# 15_FE_PORT_1-8.net
KiCad netlist of a schematic drawn in Altium Designer
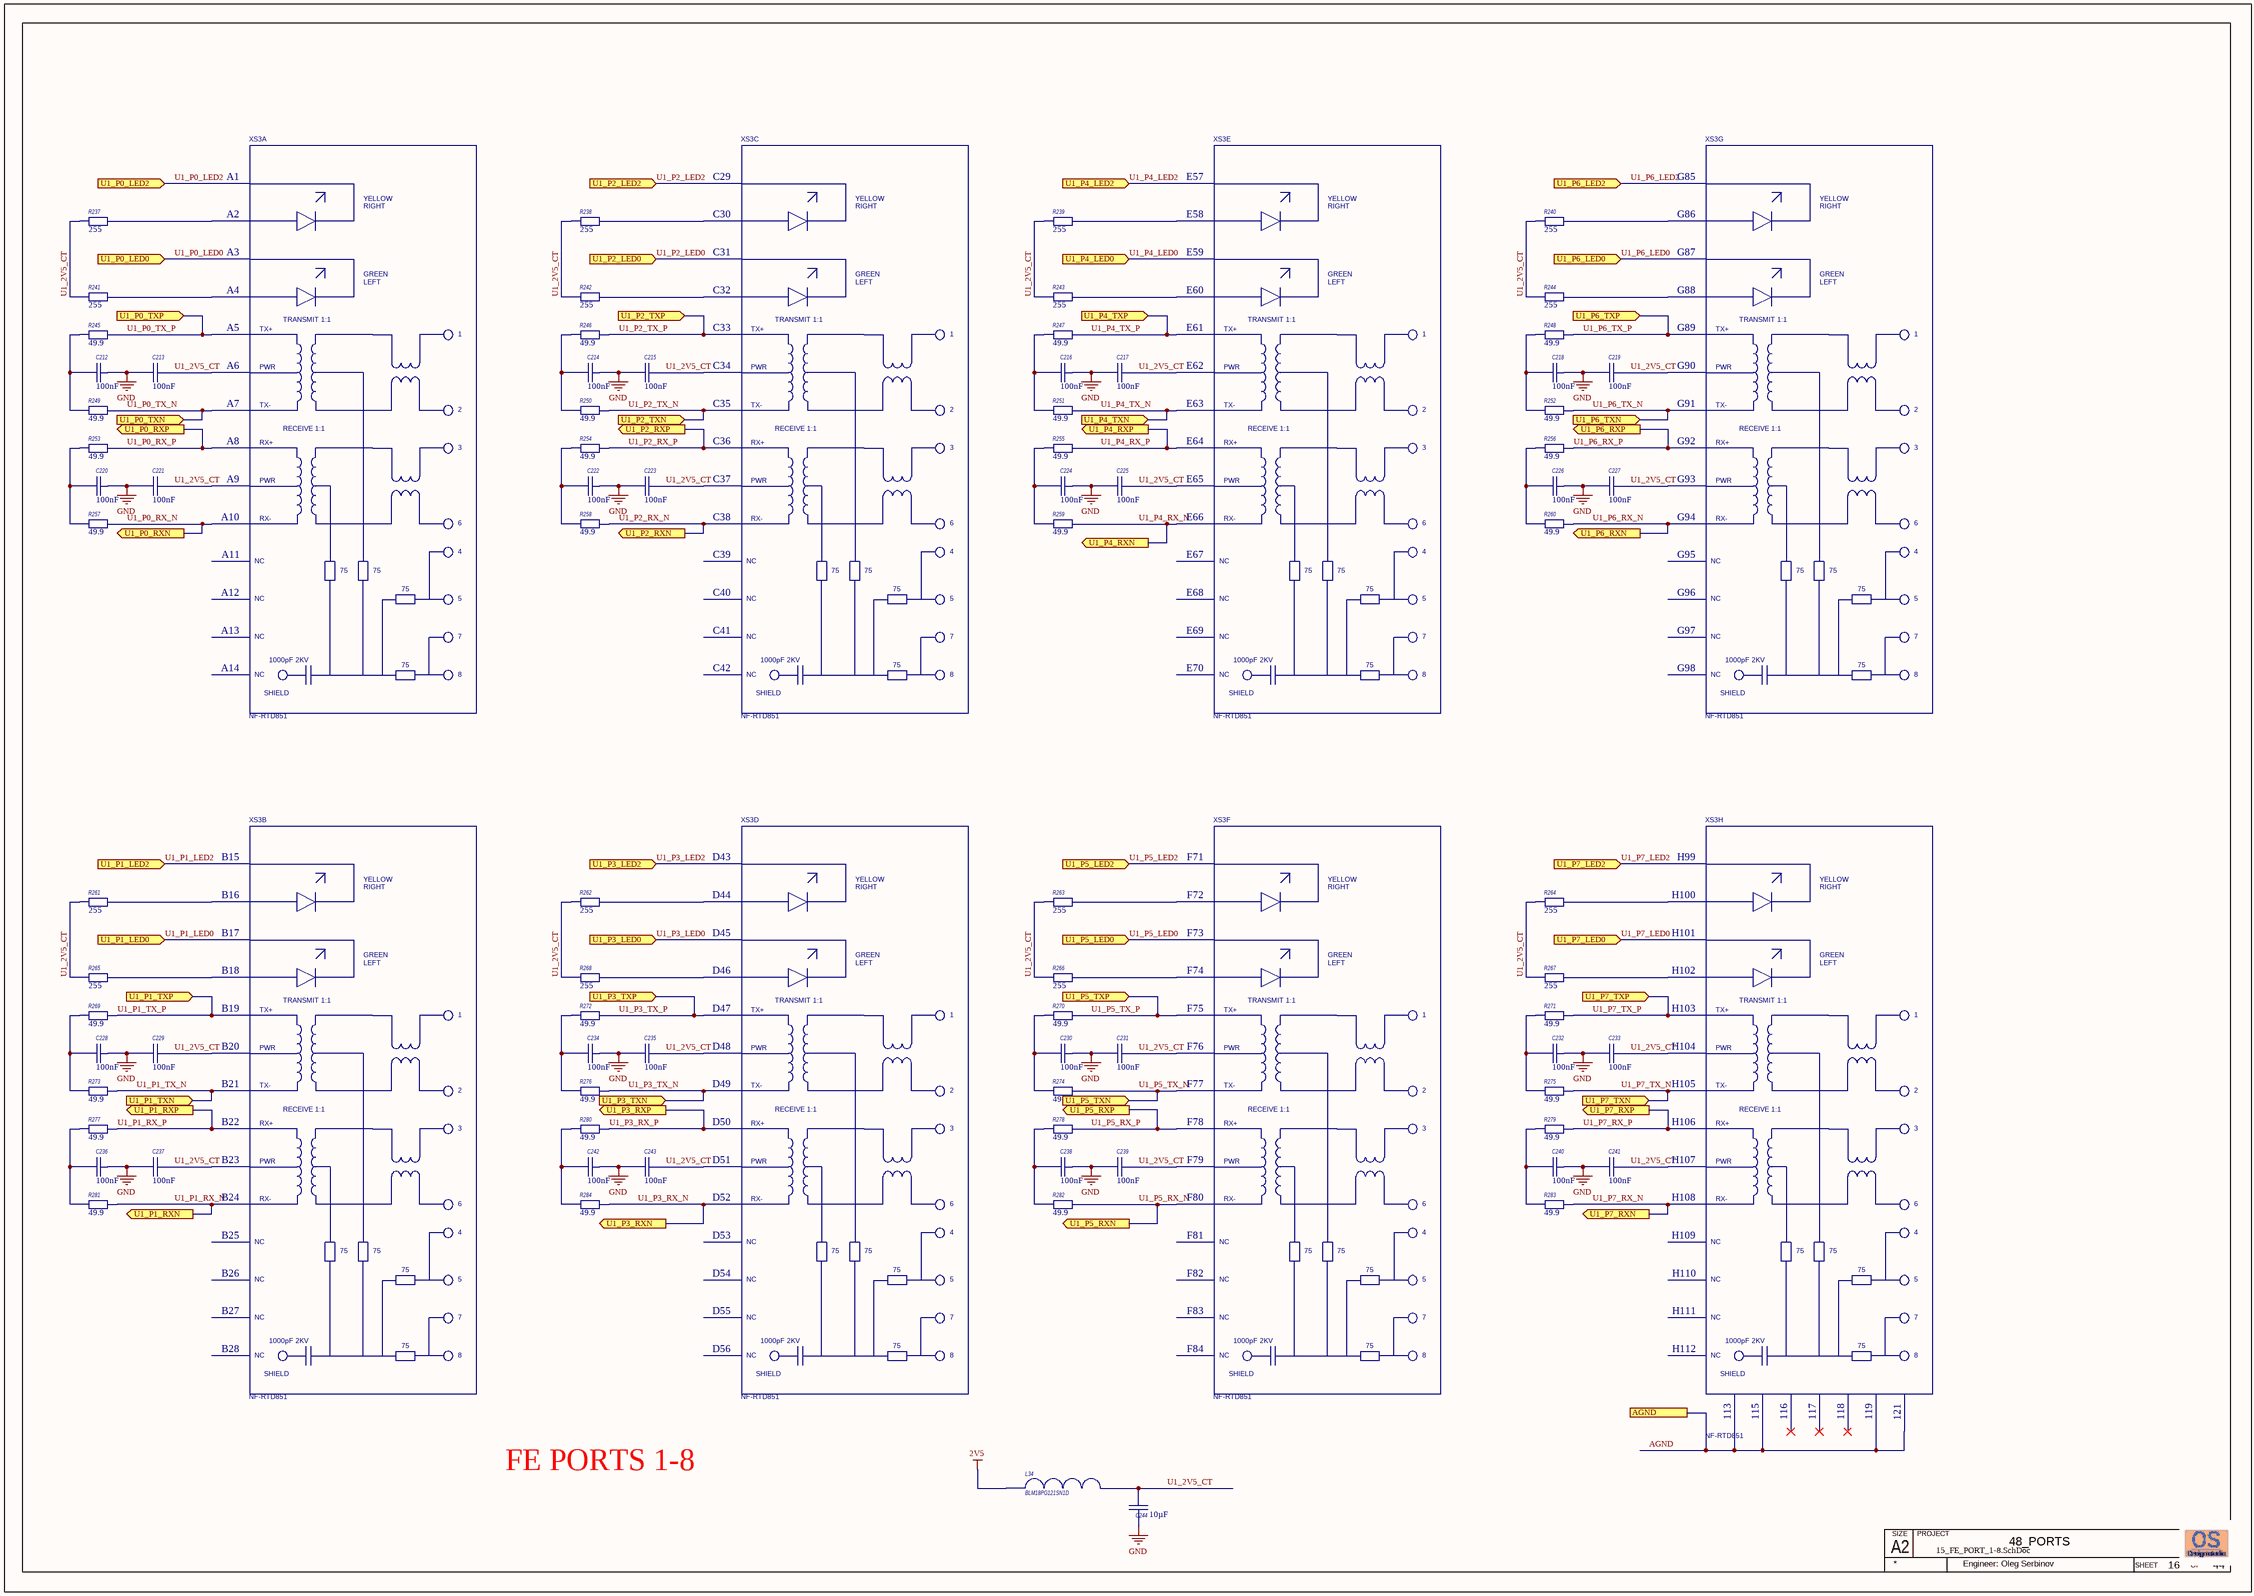
[diagram p0: 15_FE_PORT_1-8.SchDoc]

(export (version "E")
  (design (tool "Eeschema 10.0.6"))
  (components
    (comp (ref "C212")
      (value "GRM155R71E104KE14D")
      (footprint "C0402_IPC High Density")
      (description "C0402, 100nF, 25V, X7R")
      (fields
        (field (name "MANUFACTURER") "Murata")
        (field (name "CAPACITANCE") "100nF")
        (field (name "CUSTOMER PART NUMBER") "Конденсатор, 100n, 0402, 25V, X7R, 10%")
      )
      (libsource (lib "CAPACITORS") (part "GRM155R71E104KE14D"))
    )
    (comp (ref "C213")
      (value "GRM155R71E104KE14D")
      (footprint "C0402_IPC High Density")
      (description "C0402, 100nF, 25V, X7R")
      (fields
        (field (name "MANUFACTURER") "Murata")
        (field (name "CAPACITANCE") "100nF")
        (field (name "CUSTOMER PART NUMBER") "Конденсатор, 100n, 0402, 25V, X7R, 10%")
      )
      (libsource (lib "CAPACITORS") (part "GRM155R71E104KE14D"))
    )
    (comp (ref "C214")
      (value "GRM155R71E104KE14D")
      (footprint "C0402_IPC High Density")
      (description "C0402, 100nF, 25V, X7R")
      (fields
        (field (name "MANUFACTURER") "Murata")
        (field (name "CAPACITANCE") "100nF")
        (field (name "CUSTOMER PART NUMBER") "Конденсатор, 100n, 0402, 25V, X7R, 10%")
      )
      (libsource (lib "CAPACITORS") (part "GRM155R71E104KE14D"))
    )
    (comp (ref "C215")
      (value "GRM155R71E104KE14D")
      (footprint "C0402_IPC High Density")
      (description "C0402, 100nF, 25V, X7R")
      (fields
        (field (name "MANUFACTURER") "Murata")
        (field (name "CAPACITANCE") "100nF")
        (field (name "CUSTOMER PART NUMBER") "Конденсатор, 100n, 0402, 25V, X7R, 10%")
      )
      (libsource (lib "CAPACITORS") (part "GRM155R71E104KE14D"))
    )
    (comp (ref "C216")
      (value "GRM155R71E104KE14D")
      (footprint "C0402_IPC High Density")
      (description "C0402, 100nF, 25V, X7R")
      (fields
        (field (name "MANUFACTURER") "Murata")
        (field (name "CAPACITANCE") "100nF")
        (field (name "CUSTOMER PART NUMBER") "Конденсатор, 100n, 0402, 25V, X7R, 10%")
      )
      (libsource (lib "CAPACITORS") (part "GRM155R71E104KE14D"))
    )
    (comp (ref "C217")
      (value "GRM155R71E104KE14D")
      (footprint "C0402_IPC High Density")
      (description "C0402, 100nF, 25V, X7R")
      (fields
        (field (name "MANUFACTURER") "Murata")
        (field (name "CAPACITANCE") "100nF")
        (field (name "CUSTOMER PART NUMBER") "Конденсатор, 100n, 0402, 25V, X7R, 10%")
      )
      (libsource (lib "CAPACITORS") (part "GRM155R71E104KE14D"))
    )
    (comp (ref "C218")
      (value "GRM155R71E104KE14D")
      (footprint "C0402_IPC High Density")
      (description "C0402, 100nF, 25V, X7R")
      (fields
        (field (name "MANUFACTURER") "Murata")
        (field (name "CAPACITANCE") "100nF")
        (field (name "CUSTOMER PART NUMBER") "Конденсатор, 100n, 0402, 25V, X7R, 10%")
      )
      (libsource (lib "CAPACITORS") (part "GRM155R71E104KE14D"))
    )
    (comp (ref "C219")
      (value "GRM155R71E104KE14D")
      (footprint "C0402_IPC High Density")
      (description "C0402, 100nF, 25V, X7R")
      (fields
        (field (name "MANUFACTURER") "Murata")
        (field (name "CAPACITANCE") "100nF")
        (field (name "CUSTOMER PART NUMBER") "Конденсатор, 100n, 0402, 25V, X7R, 10%")
      )
      (libsource (lib "CAPACITORS") (part "GRM155R71E104KE14D"))
    )
    (comp (ref "C220")
      (value "GRM155R71E104KE14D")
      (footprint "C0402_IPC High Density")
      (description "C0402, 100nF, 25V, X7R")
      (fields
        (field (name "MANUFACTURER") "Murata")
        (field (name "CAPACITANCE") "100nF")
        (field (name "CUSTOMER PART NUMBER") "Конденсатор, 100n, 0402, 25V, X7R, 10%")
      )
      (libsource (lib "CAPACITORS") (part "GRM155R71E104KE14D"))
    )
    (comp (ref "C221")
      (value "GRM155R71E104KE14D")
      (footprint "C0402_IPC High Density")
      (description "C0402, 100nF, 25V, X7R")
      (fields
        (field (name "MANUFACTURER") "Murata")
        (field (name "CAPACITANCE") "100nF")
        (field (name "CUSTOMER PART NUMBER") "Конденсатор, 100n, 0402, 25V, X7R, 10%")
      )
      (libsource (lib "CAPACITORS") (part "GRM155R71E104KE14D"))
    )
    (comp (ref "C222")
      (value "GRM155R71E104KE14D")
      (footprint "C0402_IPC High Density")
      (description "C0402, 100nF, 25V, X7R")
      (fields
        (field (name "MANUFACTURER") "Murata")
        (field (name "CAPACITANCE") "100nF")
        (field (name "CUSTOMER PART NUMBER") "Конденсатор, 100n, 0402, 25V, X7R, 10%")
      )
      (libsource (lib "CAPACITORS") (part "GRM155R71E104KE14D"))
    )
    (comp (ref "C223")
      (value "GRM155R71E104KE14D")
      (footprint "C0402_IPC High Density")
      (description "C0402, 100nF, 25V, X7R")
      (fields
        (field (name "MANUFACTURER") "Murata")
        (field (name "CAPACITANCE") "100nF")
        (field (name "CUSTOMER PART NUMBER") "Конденсатор, 100n, 0402, 25V, X7R, 10%")
      )
      (libsource (lib "CAPACITORS") (part "GRM155R71E104KE14D"))
    )
    (comp (ref "C224")
      (value "GRM155R71E104KE14D")
      (footprint "C0402_IPC High Density")
      (description "C0402, 100nF, 25V, X7R")
      (fields
        (field (name "MANUFACTURER") "Murata")
        (field (name "CAPACITANCE") "100nF")
        (field (name "CUSTOMER PART NUMBER") "Конденсатор, 100n, 0402, 25V, X7R, 10%")
      )
      (libsource (lib "CAPACITORS") (part "GRM155R71E104KE14D"))
    )
    (comp (ref "C225")
      (value "GRM155R71E104KE14D")
      (footprint "C0402_IPC High Density")
      (description "C0402, 100nF, 25V, X7R")
      (fields
        (field (name "MANUFACTURER") "Murata")
        (field (name "CAPACITANCE") "100nF")
        (field (name "CUSTOMER PART NUMBER") "Конденсатор, 100n, 0402, 25V, X7R, 10%")
      )
      (libsource (lib "CAPACITORS") (part "GRM155R71E104KE14D"))
    )
    (comp (ref "C226")
      (value "GRM155R71E104KE14D")
      (footprint "C0402_IPC High Density")
      (description "C0402, 100nF, 25V, X7R")
      (fields
        (field (name "MANUFACTURER") "Murata")
        (field (name "CAPACITANCE") "100nF")
        (field (name "CUSTOMER PART NUMBER") "Конденсатор, 100n, 0402, 25V, X7R, 10%")
      )
      (libsource (lib "CAPACITORS") (part "GRM155R71E104KE14D"))
    )
    (comp (ref "C227")
      (value "GRM155R71E104KE14D")
      (footprint "C0402_IPC High Density")
      (description "C0402, 100nF, 25V, X7R")
      (fields
        (field (name "MANUFACTURER") "Murata")
        (field (name "CAPACITANCE") "100nF")
        (field (name "CUSTOMER PART NUMBER") "Конденсатор, 100n, 0402, 25V, X7R, 10%")
      )
      (libsource (lib "CAPACITORS") (part "GRM155R71E104KE14D"))
    )
    (comp (ref "C228")
      (value "GRM155R71E104KE14D")
      (footprint "C0402_IPC High Density")
      (description "C0402, 100nF, 25V, X7R")
      (fields
        (field (name "MANUFACTURER") "Murata")
        (field (name "CAPACITANCE") "100nF")
        (field (name "CUSTOMER PART NUMBER") "Конденсатор, 100n, 0402, 25V, X7R, 10%")
      )
      (libsource (lib "CAPACITORS") (part "GRM155R71E104KE14D"))
    )
    (comp (ref "C229")
      (value "GRM155R71E104KE14D")
      (footprint "C0402_IPC High Density")
      (description "C0402, 100nF, 25V, X7R")
      (fields
        (field (name "MANUFACTURER") "Murata")
        (field (name "CAPACITANCE") "100nF")
        (field (name "CUSTOMER PART NUMBER") "Конденсатор, 100n, 0402, 25V, X7R, 10%")
      )
      (libsource (lib "CAPACITORS") (part "GRM155R71E104KE14D"))
    )
    (comp (ref "C230")
      (value "GRM155R71E104KE14D")
      (footprint "C0402_IPC High Density")
      (description "C0402, 100nF, 25V, X7R")
      (fields
        (field (name "MANUFACTURER") "Murata")
        (field (name "CAPACITANCE") "100nF")
        (field (name "CUSTOMER PART NUMBER") "Конденсатор, 100n, 0402, 25V, X7R, 10%")
      )
      (libsource (lib "CAPACITORS") (part "GRM155R71E104KE14D"))
    )
    (comp (ref "C231")
      (value "GRM155R71E104KE14D")
      (footprint "C0402_IPC High Density")
      (description "C0402, 100nF, 25V, X7R")
      (fields
        (field (name "MANUFACTURER") "Murata")
        (field (name "CAPACITANCE") "100nF")
        (field (name "CUSTOMER PART NUMBER") "Конденсатор, 100n, 0402, 25V, X7R, 10%")
      )
      (libsource (lib "CAPACITORS") (part "GRM155R71E104KE14D"))
    )
    (comp (ref "C232")
      (value "GRM155R71E104KE14D")
      (footprint "C0402_IPC High Density")
      (description "C0402, 100nF, 25V, X7R")
      (fields
        (field (name "MANUFACTURER") "Murata")
        (field (name "CAPACITANCE") "100nF")
        (field (name "CUSTOMER PART NUMBER") "Конденсатор, 100n, 0402, 25V, X7R, 10%")
      )
      (libsource (lib "CAPACITORS") (part "GRM155R71E104KE14D"))
    )
    (comp (ref "C233")
      (value "GRM155R71E104KE14D")
      (footprint "C0402_IPC High Density")
      (description "C0402, 100nF, 25V, X7R")
      (fields
        (field (name "MANUFACTURER") "Murata")
        (field (name "CAPACITANCE") "100nF")
        (field (name "CUSTOMER PART NUMBER") "Конденсатор, 100n, 0402, 25V, X7R, 10%")
      )
      (libsource (lib "CAPACITORS") (part "GRM155R71E104KE14D"))
    )
    (comp (ref "C234")
      (value "GRM155R71E104KE14D")
      (footprint "C0402_IPC High Density")
      (description "C0402, 100nF, 25V, X7R")
      (fields
        (field (name "MANUFACTURER") "Murata")
        (field (name "CAPACITANCE") "100nF")
        (field (name "CUSTOMER PART NUMBER") "Конденсатор, 100n, 0402, 25V, X7R, 10%")
      )
      (libsource (lib "CAPACITORS") (part "GRM155R71E104KE14D"))
    )
    (comp (ref "C235")
      (value "GRM155R71E104KE14D")
      (footprint "C0402_IPC High Density")
      (description "C0402, 100nF, 25V, X7R")
      (fields
        (field (name "MANUFACTURER") "Murata")
        (field (name "CAPACITANCE") "100nF")
        (field (name "CUSTOMER PART NUMBER") "Конденсатор, 100n, 0402, 25V, X7R, 10%")
      )
      (libsource (lib "CAPACITORS") (part "GRM155R71E104KE14D"))
    )
    (comp (ref "C236")
      (value "GRM155R71E104KE14D")
      (footprint "C0402_IPC High Density")
      (description "C0402, 100nF, 25V, X7R")
      (fields
        (field (name "MANUFACTURER") "Murata")
        (field (name "CAPACITANCE") "100nF")
        (field (name "CUSTOMER PART NUMBER") "Конденсатор, 100n, 0402, 25V, X7R, 10%")
      )
      (libsource (lib "CAPACITORS") (part "GRM155R71E104KE14D"))
    )
    (comp (ref "C237")
      (value "GRM155R71E104KE14D")
      (footprint "C0402_IPC High Density")
      (description "C0402, 100nF, 25V, X7R")
      (fields
        (field (name "MANUFACTURER") "Murata")
        (field (name "CAPACITANCE") "100nF")
        (field (name "CUSTOMER PART NUMBER") "Конденсатор, 100n, 0402, 25V, X7R, 10%")
      )
      (libsource (lib "CAPACITORS") (part "GRM155R71E104KE14D"))
    )
    (comp (ref "C238")
      (value "GRM155R71E104KE14D")
      (footprint "C0402_IPC High Density")
      (description "C0402, 100nF, 25V, X7R")
      (fields
        (field (name "MANUFACTURER") "Murata")
        (field (name "CAPACITANCE") "100nF")
        (field (name "CUSTOMER PART NUMBER") "Конденсатор, 100n, 0402, 25V, X7R, 10%")
      )
      (libsource (lib "CAPACITORS") (part "GRM155R71E104KE14D"))
    )
    (comp (ref "C239")
      (value "GRM155R71E104KE14D")
      (footprint "C0402_IPC High Density")
      (description "C0402, 100nF, 25V, X7R")
      (fields
        (field (name "MANUFACTURER") "Murata")
        (field (name "CAPACITANCE") "100nF")
        (field (name "CUSTOMER PART NUMBER") "Конденсатор, 100n, 0402, 25V, X7R, 10%")
      )
      (libsource (lib "CAPACITORS") (part "GRM155R71E104KE14D"))
    )
    (comp (ref "C240")
      (value "GRM155R71E104KE14D")
      (footprint "C0402_IPC High Density")
      (description "C0402, 100nF, 25V, X7R")
      (fields
        (field (name "MANUFACTURER") "Murata")
        (field (name "CAPACITANCE") "100nF")
        (field (name "CUSTOMER PART NUMBER") "Конденсатор, 100n, 0402, 25V, X7R, 10%")
      )
      (libsource (lib "CAPACITORS") (part "GRM155R71E104KE14D"))
    )
    (comp (ref "C241")
      (value "GRM155R71E104KE14D")
      (footprint "C0402_IPC High Density")
      (description "C0402, 100nF, 25V, X7R")
      (fields
        (field (name "MANUFACTURER") "Murata")
        (field (name "CAPACITANCE") "100nF")
        (field (name "CUSTOMER PART NUMBER") "Конденсатор, 100n, 0402, 25V, X7R, 10%")
      )
      (libsource (lib "CAPACITORS") (part "GRM155R71E104KE14D"))
    )
    (comp (ref "C242")
      (value "GRM155R71E104KE14D")
      (footprint "C0402_IPC High Density")
      (description "C0402, 100nF, 25V, X7R")
      (fields
        (field (name "MANUFACTURER") "Murata")
        (field (name "CAPACITANCE") "100nF")
        (field (name "CUSTOMER PART NUMBER") "Конденсатор, 100n, 0402, 25V, X7R, 10%")
      )
      (libsource (lib "CAPACITORS") (part "GRM155R71E104KE14D"))
    )
    (comp (ref "C243")
      (value "GRM155R71E104KE14D")
      (footprint "C0402_IPC High Density")
      (description "C0402, 100nF, 25V, X7R")
      (fields
        (field (name "MANUFACTURER") "Murata")
        (field (name "CAPACITANCE") "100nF")
        (field (name "CUSTOMER PART NUMBER") "Конденсатор, 100n, 0402, 25V, X7R, 10%")
      )
      (libsource (lib "CAPACITORS") (part "GRM155R71E104KE14D"))
    )
    (comp (ref "C244")
      (value "GRM21BR61C106KE15")
      (footprint "CAPC2012[0805]")
      (description "C0805, 10uF 10%, 16V, X5R")
      (fields
        (field (name "MANUFACTURER") "Murata")
        (field (name "TOLERANCE") "±10%")
        (field (name "CAPACITANCE") "10µF")
      )
      (libsource (lib "CAPACITORS") (part "GRM21BR61C106KE15"))
    )
    (comp (ref "L34")
      (value "BLM18PG121SN1D")
      (footprint "INDC1608X95N")
      (description "FILTER BLM18 (0603, 2A)")
      (fields
        (field (name "MANUFACTURER") "Murata")
        (field (name "RPART NUMBER") "MPZ1608S121ATAH0 ; CIC10P121NC ; MPZ1608S121ATDH5 ; BLM18PG121SH1D ; 742792625")
      )
      (libsource (lib "INDUCTORS") (part "BLM18PG121SN1D"))
    )
    (comp (ref "R237")
      (value "ERJ-2RKF2550X")
      (footprint "RESC1005[0402]")
      (description "R0402, 255R 1%")
      (fields
        (field (name "MANUFACTURER") "Panasonic")
        (field (name "TOLERANCE") "±1%")
        (field (name "RESISTANCE (OHMS)") "255")
      )
      (libsource (lib "RESISTOR") (part "ERJ-2RKF2550X"))
    )
    (comp (ref "R238")
      (value "ERJ-2RKF2550X")
      (footprint "RESC1005[0402]")
      (description "R0402, 255R 1%")
      (fields
        (field (name "MANUFACTURER") "Panasonic")
        (field (name "TOLERANCE") "±1%")
        (field (name "RESISTANCE (OHMS)") "255")
      )
      (libsource (lib "RESISTOR") (part "ERJ-2RKF2550X"))
    )
    (comp (ref "R239")
      (value "ERJ-2RKF2550X")
      (footprint "RESC1005[0402]")
      (description "R0402, 255R 1%")
      (fields
        (field (name "MANUFACTURER") "Panasonic")
        (field (name "TOLERANCE") "±1%")
        (field (name "RESISTANCE (OHMS)") "255")
      )
      (libsource (lib "RESISTOR") (part "ERJ-2RKF2550X"))
    )
    (comp (ref "R240")
      (value "ERJ-2RKF2550X")
      (footprint "RESC1005[0402]")
      (description "R0402, 255R 1%")
      (fields
        (field (name "MANUFACTURER") "Panasonic")
        (field (name "TOLERANCE") "±1%")
        (field (name "RESISTANCE (OHMS)") "255")
      )
      (libsource (lib "RESISTOR") (part "ERJ-2RKF2550X"))
    )
    (comp (ref "R241")
      (value "ERJ-2RKF2550X")
      (footprint "RESC1005[0402]")
      (description "R0402, 255R 1%")
      (fields
        (field (name "MANUFACTURER") "Panasonic")
        (field (name "TOLERANCE") "±1%")
        (field (name "RESISTANCE (OHMS)") "255")
      )
      (libsource (lib "RESISTOR") (part "ERJ-2RKF2550X"))
    )
    (comp (ref "R242")
      (value "ERJ-2RKF2550X")
      (footprint "RESC1005[0402]")
      (description "R0402, 255R 1%")
      (fields
        (field (name "MANUFACTURER") "Panasonic")
        (field (name "TOLERANCE") "±1%")
        (field (name "RESISTANCE (OHMS)") "255")
      )
      (libsource (lib "RESISTOR") (part "ERJ-2RKF2550X"))
    )
    (comp (ref "R243")
      (value "ERJ-2RKF2550X")
      (footprint "RESC1005[0402]")
      (description "R0402, 255R 1%")
      (fields
        (field (name "MANUFACTURER") "Panasonic")
        (field (name "TOLERANCE") "±1%")
        (field (name "RESISTANCE (OHMS)") "255")
      )
      (libsource (lib "RESISTOR") (part "ERJ-2RKF2550X"))
    )
    (comp (ref "R244")
      (value "ERJ-2RKF2550X")
      (footprint "RESC1005[0402]")
      (description "R0402, 255R 1%")
      (fields
        (field (name "MANUFACTURER") "Panasonic")
        (field (name "TOLERANCE") "±1%")
        (field (name "RESISTANCE (OHMS)") "255")
      )
      (libsource (lib "RESISTOR") (part "ERJ-2RKF2550X"))
    )
    (comp (ref "R245")
      (value "ERJ-2RKF49R9X")
      (footprint "R0402_IPC High Density")
      (description "R0402, 49.9R 1%")
      (fields
        (field (name "MANUFACTURER") "Panasonic")
        (field (name "TOLERANCE") "1 %")
        (field (name "RESISTANCE") "49.9")
      )
      (libsource (lib "RESISTOR") (part "ERJ-2RKF49R9X"))
    )
    (comp (ref "R246")
      (value "ERJ-2RKF49R9X")
      (footprint "R0402_IPC High Density")
      (description "R0402, 49.9R 1%")
      (fields
        (field (name "MANUFACTURER") "Panasonic")
        (field (name "TOLERANCE") "1 %")
        (field (name "RESISTANCE") "49.9")
      )
      (libsource (lib "RESISTOR") (part "ERJ-2RKF49R9X"))
    )
    (comp (ref "R247")
      (value "ERJ-2RKF49R9X")
      (footprint "R0402_IPC High Density")
      (description "R0402, 49.9R 1%")
      (fields
        (field (name "MANUFACTURER") "Panasonic")
        (field (name "TOLERANCE") "1 %")
        (field (name "RESISTANCE") "49.9")
      )
      (libsource (lib "RESISTOR") (part "ERJ-2RKF49R9X"))
    )
    (comp (ref "R248")
      (value "ERJ-2RKF49R9X")
      (footprint "R0402_IPC High Density")
      (description "R0402, 49.9R 1%")
      (fields
        (field (name "MANUFACTURER") "Panasonic")
        (field (name "TOLERANCE") "1 %")
        (field (name "RESISTANCE") "49.9")
      )
      (libsource (lib "RESISTOR") (part "ERJ-2RKF49R9X"))
    )
    (comp (ref "R249")
      (value "ERJ-2RKF49R9X")
      (footprint "R0402_IPC High Density")
      (description "R0402, 49.9R 1%")
      (fields
        (field (name "MANUFACTURER") "Panasonic")
        (field (name "TOLERANCE") "1 %")
        (field (name "RESISTANCE") "49.9")
      )
      (libsource (lib "RESISTOR") (part "ERJ-2RKF49R9X"))
    )
    (comp (ref "R250")
      (value "ERJ-2RKF49R9X")
      (footprint "R0402_IPC High Density")
      (description "R0402, 49.9R 1%")
      (fields
        (field (name "MANUFACTURER") "Panasonic")
        (field (name "TOLERANCE") "1 %")
        (field (name "RESISTANCE") "49.9")
      )
      (libsource (lib "RESISTOR") (part "ERJ-2RKF49R9X"))
    )
    (comp (ref "R251")
      (value "ERJ-2RKF49R9X")
      (footprint "R0402_IPC High Density")
      (description "R0402, 49.9R 1%")
      (fields
        (field (name "MANUFACTURER") "Panasonic")
        (field (name "TOLERANCE") "1 %")
        (field (name "RESISTANCE") "49.9")
      )
      (libsource (lib "RESISTOR") (part "ERJ-2RKF49R9X"))
    )
    (comp (ref "R252")
      (value "ERJ-2RKF49R9X")
      (footprint "R0402_IPC High Density")
      (description "R0402, 49.9R 1%")
      (fields
        (field (name "MANUFACTURER") "Panasonic")
        (field (name "TOLERANCE") "1 %")
        (field (name "RESISTANCE") "49.9")
      )
      (libsource (lib "RESISTOR") (part "ERJ-2RKF49R9X"))
    )
    (comp (ref "R253")
      (value "ERJ-2RKF49R9X")
      (footprint "R0402_IPC High Density")
      (description "R0402, 49.9R 1%")
      (fields
        (field (name "MANUFACTURER") "Panasonic")
        (field (name "TOLERANCE") "1 %")
        (field (name "RESISTANCE") "49.9")
      )
      (libsource (lib "RESISTOR") (part "ERJ-2RKF49R9X"))
    )
    (comp (ref "R254")
      (value "ERJ-2RKF49R9X")
      (footprint "R0402_IPC High Density")
      (description "R0402, 49.9R 1%")
      (fields
        (field (name "MANUFACTURER") "Panasonic")
        (field (name "TOLERANCE") "1 %")
        (field (name "RESISTANCE") "49.9")
      )
      (libsource (lib "RESISTOR") (part "ERJ-2RKF49R9X"))
    )
    (comp (ref "R255")
      (value "ERJ-2RKF49R9X")
      (footprint "R0402_IPC High Density")
      (description "R0402, 49.9R 1%")
      (fields
        (field (name "MANUFACTURER") "Panasonic")
        (field (name "TOLERANCE") "1 %")
        (field (name "RESISTANCE") "49.9")
      )
      (libsource (lib "RESISTOR") (part "ERJ-2RKF49R9X"))
    )
    (comp (ref "R256")
      (value "ERJ-2RKF49R9X")
      (footprint "R0402_IPC High Density")
      (description "R0402, 49.9R 1%")
      (fields
        (field (name "MANUFACTURER") "Panasonic")
        (field (name "TOLERANCE") "1 %")
        (field (name "RESISTANCE") "49.9")
      )
      (libsource (lib "RESISTOR") (part "ERJ-2RKF49R9X"))
    )
    (comp (ref "R257")
      (value "ERJ-2RKF49R9X")
      (footprint "R0402_IPC High Density")
      (description "R0402, 49.9R 1%")
      (fields
        (field (name "MANUFACTURER") "Panasonic")
        (field (name "TOLERANCE") "1 %")
        (field (name "RESISTANCE") "49.9")
      )
      (libsource (lib "RESISTOR") (part "ERJ-2RKF49R9X"))
    )
    (comp (ref "R258")
      (value "ERJ-2RKF49R9X")
      (footprint "R0402_IPC High Density")
      (description "R0402, 49.9R 1%")
      (fields
        (field (name "MANUFACTURER") "Panasonic")
        (field (name "TOLERANCE") "1 %")
        (field (name "RESISTANCE") "49.9")
      )
      (libsource (lib "RESISTOR") (part "ERJ-2RKF49R9X"))
    )
    (comp (ref "R259")
      (value "ERJ-2RKF49R9X")
      (footprint "R0402_IPC High Density")
      (description "R0402, 49.9R 1%")
      (fields
        (field (name "MANUFACTURER") "Panasonic")
        (field (name "TOLERANCE") "1 %")
        (field (name "RESISTANCE") "49.9")
      )
      (libsource (lib "RESISTOR") (part "ERJ-2RKF49R9X"))
    )
    (comp (ref "R260")
      (value "ERJ-2RKF49R9X")
      (footprint "R0402_IPC High Density")
      (description "R0402, 49.9R 1%")
      (fields
        (field (name "MANUFACTURER") "Panasonic")
        (field (name "TOLERANCE") "1 %")
        (field (name "RESISTANCE") "49.9")
      )
      (libsource (lib "RESISTOR") (part "ERJ-2RKF49R9X"))
    )
    (comp (ref "R261")
      (value "ERJ-2RKF2550X")
      (footprint "RESC1005[0402]")
      (description "R0402, 255R 1%")
      (fields
        (field (name "MANUFACTURER") "Panasonic")
        (field (name "TOLERANCE") "±1%")
        (field (name "RESISTANCE (OHMS)") "255")
      )
      (libsource (lib "RESISTOR") (part "ERJ-2RKF2550X"))
    )
    (comp (ref "R262")
      (value "ERJ-2RKF2550X")
      (footprint "RESC1005[0402]")
      (description "R0402, 255R 1%")
      (fields
        (field (name "MANUFACTURER") "Panasonic")
        (field (name "TOLERANCE") "±1%")
        (field (name "RESISTANCE (OHMS)") "255")
      )
      (libsource (lib "RESISTOR") (part "ERJ-2RKF2550X"))
    )
    (comp (ref "R263")
      (value "ERJ-2RKF2550X")
      (footprint "RESC1005[0402]")
      (description "R0402, 255R 1%")
      (fields
        (field (name "MANUFACTURER") "Panasonic")
        (field (name "TOLERANCE") "±1%")
        (field (name "RESISTANCE (OHMS)") "255")
      )
      (libsource (lib "RESISTOR") (part "ERJ-2RKF2550X"))
    )
    (comp (ref "R264")
      (value "ERJ-2RKF2550X")
      (footprint "RESC1005[0402]")
      (description "R0402, 255R 1%")
      (fields
        (field (name "MANUFACTURER") "Panasonic")
        (field (name "TOLERANCE") "±1%")
        (field (name "RESISTANCE (OHMS)") "255")
      )
      (libsource (lib "RESISTOR") (part "ERJ-2RKF2550X"))
    )
    (comp (ref "R265")
      (value "ERJ-2RKF2550X")
      (footprint "RESC1005[0402]")
      (description "R0402, 255R 1%")
      (fields
        (field (name "MANUFACTURER") "Panasonic")
        (field (name "TOLERANCE") "±1%")
        (field (name "RESISTANCE (OHMS)") "255")
      )
      (libsource (lib "RESISTOR") (part "ERJ-2RKF2550X"))
    )
    (comp (ref "R266")
      (value "ERJ-2RKF2550X")
      (footprint "RESC1005[0402]")
      (description "R0402, 255R 1%")
      (fields
        (field (name "MANUFACTURER") "Panasonic")
        (field (name "TOLERANCE") "±1%")
        (field (name "RESISTANCE (OHMS)") "255")
      )
      (libsource (lib "RESISTOR") (part "ERJ-2RKF2550X"))
    )
    (comp (ref "R267")
      (value "ERJ-2RKF2550X")
      (footprint "RESC1005[0402]")
      (description "R0402, 255R 1%")
      (fields
        (field (name "MANUFACTURER") "Panasonic")
        (field (name "TOLERANCE") "±1%")
        (field (name "RESISTANCE (OHMS)") "255")
      )
      (libsource (lib "RESISTOR") (part "ERJ-2RKF2550X"))
    )
    (comp (ref "R268")
      (value "ERJ-2RKF2550X")
      (footprint "RESC1005[0402]")
      (description "R0402, 255R 1%")
      (fields
        (field (name "MANUFACTURER") "Panasonic")
        (field (name "TOLERANCE") "±1%")
        (field (name "RESISTANCE (OHMS)") "255")
      )
      (libsource (lib "RESISTOR") (part "ERJ-2RKF2550X"))
    )
    (comp (ref "R269")
      (value "ERJ-2RKF49R9X")
      (footprint "R0402_IPC High Density")
      (description "R0402, 49.9R 1%")
      (fields
        (field (name "MANUFACTURER") "Panasonic")
        (field (name "TOLERANCE") "1 %")
        (field (name "RESISTANCE") "49.9")
      )
      (libsource (lib "RESISTOR") (part "ERJ-2RKF49R9X"))
    )
    (comp (ref "R270")
      (value "ERJ-2RKF49R9X")
      (footprint "R0402_IPC High Density")
      (description "R0402, 49.9R 1%")
      (fields
        (field (name "MANUFACTURER") "Panasonic")
        (field (name "TOLERANCE") "1 %")
        (field (name "RESISTANCE") "49.9")
      )
      (libsource (lib "RESISTOR") (part "ERJ-2RKF49R9X"))
    )
    (comp (ref "R271")
      (value "ERJ-2RKF49R9X")
      (footprint "R0402_IPC High Density")
      (description "R0402, 49.9R 1%")
      (fields
        (field (name "MANUFACTURER") "Panasonic")
        (field (name "TOLERANCE") "1 %")
        (field (name "RESISTANCE") "49.9")
      )
      (libsource (lib "RESISTOR") (part "ERJ-2RKF49R9X"))
    )
    (comp (ref "R272")
      (value "ERJ-2RKF49R9X")
      (footprint "R0402_IPC High Density")
      (description "R0402, 49.9R 1%")
      (fields
        (field (name "MANUFACTURER") "Panasonic")
        (field (name "TOLERANCE") "1 %")
        (field (name "RESISTANCE") "49.9")
      )
      (libsource (lib "RESISTOR") (part "ERJ-2RKF49R9X"))
    )
    (comp (ref "R273")
      (value "ERJ-2RKF49R9X")
      (footprint "R0402_IPC High Density")
      (description "R0402, 49.9R 1%")
      (fields
        (field (name "MANUFACTURER") "Panasonic")
        (field (name "TOLERANCE") "1 %")
        (field (name "RESISTANCE") "49.9")
      )
      (libsource (lib "RESISTOR") (part "ERJ-2RKF49R9X"))
    )
    (comp (ref "R274")
      (value "ERJ-2RKF49R9X")
      (footprint "R0402_IPC High Density")
      (description "R0402, 49.9R 1%")
      (fields
        (field (name "MANUFACTURER") "Panasonic")
        (field (name "TOLERANCE") "1 %")
        (field (name "RESISTANCE") "49.9")
      )
      (libsource (lib "RESISTOR") (part "ERJ-2RKF49R9X"))
    )
    (comp (ref "R275")
      (value "ERJ-2RKF49R9X")
      (footprint "R0402_IPC High Density")
      (description "R0402, 49.9R 1%")
      (fields
        (field (name "MANUFACTURER") "Panasonic")
        (field (name "TOLERANCE") "1 %")
        (field (name "RESISTANCE") "49.9")
      )
      (libsource (lib "RESISTOR") (part "ERJ-2RKF49R9X"))
    )
    (comp (ref "R276")
      (value "ERJ-2RKF49R9X")
      (footprint "R0402_IPC High Density")
      (description "R0402, 49.9R 1%")
      (fields
        (field (name "MANUFACTURER") "Panasonic")
        (field (name "TOLERANCE") "1 %")
        (field (name "RESISTANCE") "49.9")
      )
      (libsource (lib "RESISTOR") (part "ERJ-2RKF49R9X"))
    )
    (comp (ref "R277")
      (value "ERJ-2RKF49R9X")
      (footprint "R0402_IPC High Density")
      (description "R0402, 49.9R 1%")
      (fields
        (field (name "MANUFACTURER") "Panasonic")
        (field (name "TOLERANCE") "1 %")
        (field (name "RESISTANCE") "49.9")
      )
      (libsource (lib "RESISTOR") (part "ERJ-2RKF49R9X"))
    )
    (comp (ref "R278")
      (value "ERJ-2RKF49R9X")
      (footprint "R0402_IPC High Density")
      (description "R0402, 49.9R 1%")
      (fields
        (field (name "MANUFACTURER") "Panasonic")
        (field (name "TOLERANCE") "1 %")
        (field (name "RESISTANCE") "49.9")
      )
      (libsource (lib "RESISTOR") (part "ERJ-2RKF49R9X"))
    )
    (comp (ref "R279")
      (value "ERJ-2RKF49R9X")
      (footprint "R0402_IPC High Density")
      (description "R0402, 49.9R 1%")
      (fields
        (field (name "MANUFACTURER") "Panasonic")
        (field (name "TOLERANCE") "1 %")
        (field (name "RESISTANCE") "49.9")
      )
      (libsource (lib "RESISTOR") (part "ERJ-2RKF49R9X"))
    )
    (comp (ref "R280")
      (value "ERJ-2RKF49R9X")
      (footprint "R0402_IPC High Density")
      (description "R0402, 49.9R 1%")
      (fields
        (field (name "MANUFACTURER") "Panasonic")
        (field (name "TOLERANCE") "1 %")
        (field (name "RESISTANCE") "49.9")
      )
      (libsource (lib "RESISTOR") (part "ERJ-2RKF49R9X"))
    )
    (comp (ref "R281")
      (value "ERJ-2RKF49R9X")
      (footprint "R0402_IPC High Density")
      (description "R0402, 49.9R 1%")
      (fields
        (field (name "MANUFACTURER") "Panasonic")
        (field (name "TOLERANCE") "1 %")
        (field (name "RESISTANCE") "49.9")
      )
      (libsource (lib "RESISTOR") (part "ERJ-2RKF49R9X"))
    )
    (comp (ref "R282")
      (value "ERJ-2RKF49R9X")
      (footprint "R0402_IPC High Density")
      (description "R0402, 49.9R 1%")
      (fields
        (field (name "MANUFACTURER") "Panasonic")
        (field (name "TOLERANCE") "1 %")
        (field (name "RESISTANCE") "49.9")
      )
      (libsource (lib "RESISTOR") (part "ERJ-2RKF49R9X"))
    )
    (comp (ref "R283")
      (value "ERJ-2RKF49R9X")
      (footprint "R0402_IPC High Density")
      (description "R0402, 49.9R 1%")
      (fields
        (field (name "MANUFACTURER") "Panasonic")
        (field (name "TOLERANCE") "1 %")
        (field (name "RESISTANCE") "49.9")
      )
      (libsource (lib "RESISTOR") (part "ERJ-2RKF49R9X"))
    )
    (comp (ref "R284")
      (value "ERJ-2RKF49R9X")
      (footprint "R0402_IPC High Density")
      (description "R0402, 49.9R 1%")
      (fields
        (field (name "MANUFACTURER") "Panasonic")
        (field (name "TOLERANCE") "1 %")
        (field (name "RESISTANCE") "49.9")
      )
      (libsource (lib "RESISTOR") (part "ERJ-2RKF49R9X"))
    )
    (comp (ref "XS3")
      (value "NF-RTD851")
      (footprint "NF-RTD851_2X4_LED_NF-RTD851_2X4_LED(Primary)")
      (description "Connector RJ45 100mb 8 ports and led  NF-RTD851")
      (fields
        (field (name "CUSTOMER PART NUMBER") "Разъем, NF-RTD851, CONN MAGJACK 8PORT 100 BASE-TX")
        (field (name "MANUFACTURER") "Shenzhen Newfly Electronics")
      )
      (libsource (lib "CONNECTORS") (part "NF-RTD851 2X4 EMI LED"))
    )
  )
  (nets
    (net (code "1") (name "/AGND") (class "Default")
      (node (ref "XS3") (pin "113") (pintype "passive"))
      (node (ref "XS3") (pin "115") (pintype "passive"))
      (node (ref "XS3") (pin "119") (pintype "passive"))
      (node (ref "XS3") (pin "121") (pintype "passive"))
    )
    (net (code "2") (name "/U1_2V5_CT") (class "Default")
      (node (ref "C213") (pin "2") (pintype "passive"))
      (node (ref "C215") (pin "2") (pintype "passive"))
      (node (ref "C217") (pin "2") (pintype "passive"))
      (node (ref "C219") (pin "2") (pintype "passive"))
      (node (ref "C221") (pin "2") (pintype "passive"))
      (node (ref "C223") (pin "2") (pintype "passive"))
      (node (ref "C225") (pin "2") (pintype "passive"))
      (node (ref "C227") (pin "2") (pintype "passive"))
      (node (ref "C229") (pin "2") (pintype "passive"))
      (node (ref "C231") (pin "2") (pintype "passive"))
      (node (ref "C233") (pin "2") (pintype "passive"))
      (node (ref "C235") (pin "2") (pintype "passive"))
      (node (ref "C237") (pin "2") (pintype "passive"))
      (node (ref "C239") (pin "2") (pintype "passive"))
      (node (ref "C241") (pin "2") (pintype "passive"))
      (node (ref "C243") (pin "2") (pintype "passive"))
      (node (ref "C244") (pin "2") (pintype "passive"))
      (node (ref "L34") (pin "2") (pinfunction "2_2") (pintype "passive"))
      (node (ref "R237") (pin "1") (pintype "passive"))
      (node (ref "R238") (pin "1") (pintype "passive"))
      (node (ref "R239") (pin "1") (pintype "passive"))
      (node (ref "R240") (pin "1") (pintype "passive"))
      (node (ref "R241") (pin "1") (pintype "passive"))
      (node (ref "R242") (pin "1") (pintype "passive"))
      (node (ref "R243") (pin "1") (pintype "passive"))
      (node (ref "R244") (pin "1") (pintype "passive"))
      (node (ref "R261") (pin "1") (pintype "passive"))
      (node (ref "R262") (pin "1") (pintype "passive"))
      (node (ref "R263") (pin "1") (pintype "passive"))
      (node (ref "R264") (pin "1") (pintype "passive"))
      (node (ref "R265") (pin "1") (pintype "passive"))
      (node (ref "R266") (pin "1") (pintype "passive"))
      (node (ref "R267") (pin "1") (pintype "passive"))
      (node (ref "R268") (pin "1") (pintype "passive"))
      (node (ref "XS3") (pin "A6") (pintype "passive"))
      (node (ref "XS3") (pin "A9") (pintype "passive"))
      (node (ref "XS3") (pin "B20") (pintype "passive"))
      (node (ref "XS3") (pin "B23") (pintype "passive"))
      (node (ref "XS3") (pin "C34") (pintype "passive"))
      (node (ref "XS3") (pin "C37") (pintype "passive"))
      (node (ref "XS3") (pin "D48") (pintype "passive"))
      (node (ref "XS3") (pin "D51") (pintype "passive"))
      (node (ref "XS3") (pin "E62") (pintype "passive"))
      (node (ref "XS3") (pin "E65") (pintype "passive"))
      (node (ref "XS3") (pin "F76") (pintype "passive"))
      (node (ref "XS3") (pin "F79") (pintype "passive"))
      (node (ref "XS3") (pin "G90") (pintype "passive"))
      (node (ref "XS3") (pin "G93") (pintype "passive"))
      (node (ref "XS3") (pin "H104") (pintype "passive"))
      (node (ref "XS3") (pin "H107") (pintype "passive"))
    )
    (net (code "3") (name "/U1_P0_LED0") (class "Default") (node (ref "XS3") (pin "A3") (pintype "passive")))
    (net (code "4") (name "/U1_P0_LED2") (class "Default") (node (ref "XS3") (pin "A1") (pintype "passive")))
    (net (code "5") (name "/U1_P0_RX_N") (class "Default")
      (node (ref "R257") (pin "2") (pintype "passive"))
      (node (ref "XS3") (pin "A10") (pintype "passive"))
    )
    (net (code "6") (name "/U1_P0_RX_P") (class "Default")
      (node (ref "R253") (pin "2") (pintype "passive"))
      (node (ref "XS3") (pin "A8") (pintype "passive"))
    )
    (net (code "7") (name "/U1_P0_TX_N") (class "Default")
      (node (ref "R249") (pin "2") (pintype "passive"))
      (node (ref "XS3") (pin "A7") (pintype "passive"))
    )
    (net (code "8") (name "/U1_P0_TX_P") (class "Default")
      (node (ref "R245") (pin "2") (pintype "passive"))
      (node (ref "XS3") (pin "A5") (pintype "passive"))
    )
    (net (code "9") (name "/U1_P1_LED0") (class "Default") (node (ref "XS3") (pin "B17") (pintype "passive")))
    (net (code "10") (name "/U1_P1_LED2") (class "Default")
      (node (ref "XS3") (pin "B15") (pintype "passive"))
    )
    (net (code "11") (name "/U1_P1_RX_N") (class "Default")
      (node (ref "R281") (pin "2") (pintype "passive"))
      (node (ref "XS3") (pin "B24") (pintype "passive"))
    )
    (net (code "12") (name "/U1_P1_RX_P") (class "Default")
      (node (ref "R277") (pin "2") (pintype "passive"))
      (node (ref "XS3") (pin "B22") (pintype "passive"))
    )
    (net (code "13") (name "/U1_P1_TX_N") (class "Default")
      (node (ref "R273") (pin "2") (pintype "passive"))
      (node (ref "XS3") (pin "B21") (pintype "passive"))
    )
    (net (code "14") (name "/U1_P1_TX_P") (class "Default")
      (node (ref "R269") (pin "2") (pintype "passive"))
      (node (ref "XS3") (pin "B19") (pintype "passive"))
    )
    (net (code "15") (name "/U1_P2_LED0") (class "Default")
      (node (ref "XS3") (pin "C31") (pintype "passive"))
    )
    (net (code "16") (name "/U1_P2_LED2") (class "Default")
      (node (ref "XS3") (pin "C29") (pintype "passive"))
    )
    (net (code "17") (name "/U1_P2_RX_N") (class "Default")
      (node (ref "R258") (pin "2") (pintype "passive"))
      (node (ref "XS3") (pin "C38") (pintype "passive"))
    )
    (net (code "18") (name "/U1_P2_RX_P") (class "Default")
      (node (ref "R254") (pin "2") (pintype "passive"))
      (node (ref "XS3") (pin "C36") (pintype "passive"))
    )
    (net (code "19") (name "/U1_P2_TX_N") (class "Default")
      (node (ref "R250") (pin "2") (pintype "passive"))
      (node (ref "XS3") (pin "C35") (pintype "passive"))
    )
    (net (code "20") (name "/U1_P2_TX_P") (class "Default")
      (node (ref "R246") (pin "2") (pintype "passive"))
      (node (ref "XS3") (pin "C33") (pintype "passive"))
    )
    (net (code "21") (name "/U1_P3_LED0") (class "Default")
      (node (ref "XS3") (pin "D45") (pintype "passive"))
    )
    (net (code "22") (name "/U1_P3_LED2") (class "Default")
      (node (ref "XS3") (pin "D43") (pintype "passive"))
    )
    (net (code "23") (name "/U1_P3_RX_N") (class "Default")
      (node (ref "R284") (pin "2") (pintype "passive"))
      (node (ref "XS3") (pin "D52") (pintype "passive"))
    )
    (net (code "24") (name "/U1_P3_RX_P") (class "Default")
      (node (ref "R280") (pin "2") (pintype "passive"))
      (node (ref "XS3") (pin "D50") (pintype "passive"))
    )
    (net (code "25") (name "/U1_P3_TX_N") (class "Default")
      (node (ref "R276") (pin "2") (pintype "passive"))
      (node (ref "XS3") (pin "D49") (pintype "passive"))
    )
    (net (code "26") (name "/U1_P3_TX_P") (class "Default")
      (node (ref "R272") (pin "2") (pintype "passive"))
      (node (ref "XS3") (pin "D47") (pintype "passive"))
    )
    (net (code "27") (name "/U1_P4_LED0") (class "Default")
      (node (ref "XS3") (pin "E59") (pintype "passive"))
    )
    (net (code "28") (name "/U1_P4_LED2") (class "Default")
      (node (ref "XS3") (pin "E57") (pintype "passive"))
    )
    (net (code "29") (name "/U1_P4_RX_N") (class "Default")
      (node (ref "R259") (pin "2") (pintype "passive"))
      (node (ref "XS3") (pin "E66") (pintype "passive"))
    )
    (net (code "30") (name "/U1_P4_RX_P") (class "Default")
      (node (ref "R255") (pin "2") (pintype "passive"))
      (node (ref "XS3") (pin "E64") (pintype "passive"))
    )
    (net (code "31") (name "/U1_P4_TX_N") (class "Default")
      (node (ref "R251") (pin "2") (pintype "passive"))
      (node (ref "XS3") (pin "E63") (pintype "passive"))
    )
    (net (code "32") (name "/U1_P4_TX_P") (class "Default")
      (node (ref "R247") (pin "2") (pintype "passive"))
      (node (ref "XS3") (pin "E61") (pintype "passive"))
    )
    (net (code "33") (name "/U1_P5_LED0") (class "Default")
      (node (ref "XS3") (pin "F73") (pintype "passive"))
    )
    (net (code "34") (name "/U1_P5_LED2") (class "Default")
      (node (ref "XS3") (pin "F71") (pintype "passive"))
    )
    (net (code "35") (name "/U1_P5_RX_N") (class "Default")
      (node (ref "R282") (pin "2") (pintype "passive"))
      (node (ref "XS3") (pin "F80") (pintype "passive"))
    )
    (net (code "36") (name "/U1_P5_RX_P") (class "Default")
      (node (ref "R278") (pin "2") (pintype "passive"))
      (node (ref "XS3") (pin "F78") (pintype "passive"))
    )
    (net (code "37") (name "/U1_P5_TX_N") (class "Default")
      (node (ref "R274") (pin "2") (pintype "passive"))
      (node (ref "XS3") (pin "F77") (pintype "passive"))
    )
    (net (code "38") (name "/U1_P5_TX_P") (class "Default")
      (node (ref "R270") (pin "2") (pintype "passive"))
      (node (ref "XS3") (pin "F75") (pintype "passive"))
    )
    (net (code "39") (name "/U1_P6_LED0") (class "Default")
      (node (ref "XS3") (pin "G87") (pintype "passive"))
    )
    (net (code "40") (name "/U1_P6_LED2") (class "Default")
      (node (ref "XS3") (pin "G85") (pintype "passive"))
    )
    (net (code "41") (name "/U1_P6_RX_N") (class "Default")
      (node (ref "R260") (pin "2") (pintype "passive"))
      (node (ref "XS3") (pin "G94") (pintype "passive"))
    )
    (net (code "42") (name "/U1_P6_RX_P") (class "Default")
      (node (ref "R256") (pin "2") (pintype "passive"))
      (node (ref "XS3") (pin "G92") (pintype "passive"))
    )
    (net (code "43") (name "/U1_P6_TX_N") (class "Default")
      (node (ref "R252") (pin "2") (pintype "passive"))
      (node (ref "XS3") (pin "G91") (pintype "passive"))
    )
    (net (code "44") (name "/U1_P6_TX_P") (class "Default")
      (node (ref "R248") (pin "2") (pintype "passive"))
      (node (ref "XS3") (pin "G89") (pintype "passive"))
    )
    (net (code "45") (name "/U1_P7_LED0") (class "Default")
      (node (ref "XS3") (pin "H101") (pintype "passive"))
    )
    (net (code "46") (name "/U1_P7_LED2") (class "Default")
      (node (ref "XS3") (pin "H99") (pintype "passive"))
    )
    (net (code "47") (name "/U1_P7_RX_N") (class "Default")
      (node (ref "R283") (pin "2") (pintype "passive"))
      (node (ref "XS3") (pin "H108") (pintype "passive"))
    )
    (net (code "48") (name "/U1_P7_RX_P") (class "Default")
      (node (ref "R279") (pin "2") (pintype "passive"))
      (node (ref "XS3") (pin "H106") (pintype "passive"))
    )
    (net (code "49") (name "/U1_P7_TX_N") (class "Default")
      (node (ref "R275") (pin "2") (pintype "passive"))
      (node (ref "XS3") (pin "H105") (pintype "passive"))
    )
    (net (code "50") (name "/U1_P7_TX_P") (class "Default")
      (node (ref "R271") (pin "2") (pintype "passive"))
      (node (ref "XS3") (pin "H103") (pintype "passive"))
    )
    (net (code "51") (name "2V5") (class "Default")
      (node (ref "L34") (pin "1") (pinfunction "1_1") (pintype "passive"))
    )
    (net (code "52") (name "GND") (class "Default")
      (node (ref "C212") (pin "2") (pintype "passive"))
      (node (ref "C213") (pin "1") (pintype "passive"))
      (node (ref "C214") (pin "2") (pintype "passive"))
      (node (ref "C215") (pin "1") (pintype "passive"))
      (node (ref "C216") (pin "2") (pintype "passive"))
      (node (ref "C217") (pin "1") (pintype "passive"))
      (node (ref "C218") (pin "2") (pintype "passive"))
      (node (ref "C219") (pin "1") (pintype "passive"))
      (node (ref "C220") (pin "2") (pintype "passive"))
      (node (ref "C221") (pin "1") (pintype "passive"))
      (node (ref "C222") (pin "2") (pintype "passive"))
      (node (ref "C223") (pin "1") (pintype "passive"))
      (node (ref "C224") (pin "2") (pintype "passive"))
      (node (ref "C225") (pin "1") (pintype "passive"))
      (node (ref "C226") (pin "2") (pintype "passive"))
      (node (ref "C227") (pin "1") (pintype "passive"))
      (node (ref "C228") (pin "2") (pintype "passive"))
      (node (ref "C229") (pin "1") (pintype "passive"))
      (node (ref "C230") (pin "2") (pintype "passive"))
      (node (ref "C231") (pin "1") (pintype "passive"))
      (node (ref "C232") (pin "2") (pintype "passive"))
      (node (ref "C233") (pin "1") (pintype "passive"))
      (node (ref "C234") (pin "2") (pintype "passive"))
      (node (ref "C235") (pin "1") (pintype "passive"))
      (node (ref "C236") (pin "2") (pintype "passive"))
      (node (ref "C237") (pin "1") (pintype "passive"))
      (node (ref "C238") (pin "2") (pintype "passive"))
      (node (ref "C239") (pin "1") (pintype "passive"))
      (node (ref "C240") (pin "2") (pintype "passive"))
      (node (ref "C241") (pin "1") (pintype "passive"))
      (node (ref "C242") (pin "2") (pintype "passive"))
      (node (ref "C243") (pin "1") (pintype "passive"))
      (node (ref "C244") (pin "1") (pintype "passive"))
    )
    (net (code "53") (name "Net-(C212-Pad1)") (class "Default")
      (node (ref "C212") (pin "1") (pintype "passive"))
      (node (ref "R245") (pin "1") (pintype "passive"))
      (node (ref "R249") (pin "1") (pintype "passive"))
    )
    (net (code "54") (name "Net-(C214-Pad1)") (class "Default")
      (node (ref "C214") (pin "1") (pintype "passive"))
      (node (ref "R246") (pin "1") (pintype "passive"))
      (node (ref "R250") (pin "1") (pintype "passive"))
    )
    (net (code "55") (name "Net-(C216-Pad1)") (class "Default")
      (node (ref "C216") (pin "1") (pintype "passive"))
      (node (ref "R247") (pin "1") (pintype "passive"))
      (node (ref "R251") (pin "1") (pintype "passive"))
    )
    (net (code "56") (name "Net-(C218-Pad1)") (class "Default")
      (node (ref "C218") (pin "1") (pintype "passive"))
      (node (ref "R248") (pin "1") (pintype "passive"))
      (node (ref "R252") (pin "1") (pintype "passive"))
    )
    (net (code "57") (name "Net-(C220-Pad1)") (class "Default")
      (node (ref "C220") (pin "1") (pintype "passive"))
      (node (ref "R253") (pin "1") (pintype "passive"))
      (node (ref "R257") (pin "1") (pintype "passive"))
    )
    (net (code "58") (name "Net-(C222-Pad1)") (class "Default")
      (node (ref "C222") (pin "1") (pintype "passive"))
      (node (ref "R254") (pin "1") (pintype "passive"))
      (node (ref "R258") (pin "1") (pintype "passive"))
    )
    (net (code "59") (name "Net-(C224-Pad1)") (class "Default")
      (node (ref "C224") (pin "1") (pintype "passive"))
      (node (ref "R255") (pin "1") (pintype "passive"))
      (node (ref "R259") (pin "1") (pintype "passive"))
    )
    (net (code "60") (name "Net-(C226-Pad1)") (class "Default")
      (node (ref "C226") (pin "1") (pintype "passive"))
      (node (ref "R256") (pin "1") (pintype "passive"))
      (node (ref "R260") (pin "1") (pintype "passive"))
    )
    (net (code "61") (name "Net-(C228-Pad1)") (class "Default")
      (node (ref "C228") (pin "1") (pintype "passive"))
      (node (ref "R269") (pin "1") (pintype "passive"))
      (node (ref "R273") (pin "1") (pintype "passive"))
    )
    (net (code "62") (name "Net-(C230-Pad1)") (class "Default")
      (node (ref "C230") (pin "1") (pintype "passive"))
      (node (ref "R270") (pin "1") (pintype "passive"))
      (node (ref "R274") (pin "1") (pintype "passive"))
    )
    (net (code "63") (name "Net-(C232-Pad1)") (class "Default")
      (node (ref "C232") (pin "1") (pintype "passive"))
      (node (ref "R271") (pin "1") (pintype "passive"))
      (node (ref "R275") (pin "1") (pintype "passive"))
    )
    (net (code "64") (name "Net-(C234-Pad1)") (class "Default")
      (node (ref "C234") (pin "1") (pintype "passive"))
      (node (ref "R272") (pin "1") (pintype "passive"))
      (node (ref "R276") (pin "1") (pintype "passive"))
    )
    (net (code "65") (name "Net-(C236-Pad1)") (class "Default")
      (node (ref "C236") (pin "1") (pintype "passive"))
      (node (ref "R277") (pin "1") (pintype "passive"))
      (node (ref "R281") (pin "1") (pintype "passive"))
    )
    (net (code "66") (name "Net-(C238-Pad1)") (class "Default")
      (node (ref "C238") (pin "1") (pintype "passive"))
      (node (ref "R278") (pin "1") (pintype "passive"))
      (node (ref "R282") (pin "1") (pintype "passive"))
    )
    (net (code "67") (name "Net-(C240-Pad1)") (class "Default")
      (node (ref "C240") (pin "1") (pintype "passive"))
      (node (ref "R279") (pin "1") (pintype "passive"))
      (node (ref "R283") (pin "1") (pintype "passive"))
    )
    (net (code "68") (name "Net-(C242-Pad1)") (class "Default")
      (node (ref "C242") (pin "1") (pintype "passive"))
      (node (ref "R280") (pin "1") (pintype "passive"))
      (node (ref "R284") (pin "1") (pintype "passive"))
    )
    (net (code "69") (name "Net-(R237-Pad2)") (class "Default")
      (node (ref "R237") (pin "2") (pintype "passive"))
      (node (ref "XS3") (pin "A2") (pintype "passive"))
    )
    (net (code "70") (name "Net-(R238-Pad2)") (class "Default")
      (node (ref "R238") (pin "2") (pintype "passive"))
      (node (ref "XS3") (pin "C30") (pintype "passive"))
    )
    (net (code "71") (name "Net-(R239-Pad2)") (class "Default")
      (node (ref "R239") (pin "2") (pintype "passive"))
      (node (ref "XS3") (pin "E58") (pintype "passive"))
    )
    (net (code "72") (name "Net-(R240-Pad2)") (class "Default")
      (node (ref "R240") (pin "2") (pintype "passive"))
      (node (ref "XS3") (pin "G86") (pintype "passive"))
    )
    (net (code "73") (name "Net-(R241-Pad2)") (class "Default")
      (node (ref "R241") (pin "2") (pintype "passive"))
      (node (ref "XS3") (pin "A4") (pintype "passive"))
    )
    (net (code "74") (name "Net-(R242-Pad2)") (class "Default")
      (node (ref "R242") (pin "2") (pintype "passive"))
      (node (ref "XS3") (pin "C32") (pintype "passive"))
    )
    (net (code "75") (name "Net-(R243-Pad2)") (class "Default")
      (node (ref "R243") (pin "2") (pintype "passive"))
      (node (ref "XS3") (pin "E60") (pintype "passive"))
    )
    (net (code "76") (name "Net-(R244-Pad2)") (class "Default")
      (node (ref "R244") (pin "2") (pintype "passive"))
      (node (ref "XS3") (pin "G88") (pintype "passive"))
    )
    (net (code "77") (name "Net-(R261-Pad2)") (class "Default")
      (node (ref "R261") (pin "2") (pintype "passive"))
      (node (ref "XS3") (pin "B16") (pintype "passive"))
    )
    (net (code "78") (name "Net-(R262-Pad2)") (class "Default")
      (node (ref "R262") (pin "2") (pintype "passive"))
      (node (ref "XS3") (pin "D44") (pintype "passive"))
    )
    (net (code "79") (name "Net-(R263-Pad2)") (class "Default")
      (node (ref "R263") (pin "2") (pintype "passive"))
      (node (ref "XS3") (pin "F72") (pintype "passive"))
    )
    (net (code "80") (name "Net-(R264-Pad2)") (class "Default")
      (node (ref "R264") (pin "2") (pintype "passive"))
      (node (ref "XS3") (pin "H100") (pintype "passive"))
    )
    (net (code "81") (name "Net-(R265-Pad2)") (class "Default")
      (node (ref "R265") (pin "2") (pintype "passive"))
      (node (ref "XS3") (pin "B18") (pintype "passive"))
    )
    (net (code "82") (name "Net-(R266-Pad2)") (class "Default")
      (node (ref "R266") (pin "2") (pintype "passive"))
      (node (ref "XS3") (pin "F74") (pintype "passive"))
    )
    (net (code "83") (name "Net-(R267-Pad2)") (class "Default")
      (node (ref "R267") (pin "2") (pintype "passive"))
      (node (ref "XS3") (pin "H102") (pintype "passive"))
    )
    (net (code "84") (name "Net-(R268-Pad2)") (class "Default")
      (node (ref "R268") (pin "2") (pintype "passive"))
      (node (ref "XS3") (pin "D46") (pintype "passive"))
    )
    (net (code "85") (name "unconnected-(XS3-Pad113)") (class "Default")
      (node (ref "XS3") (pin "113") (pintype "passive"))
    )
    (net (code "86") (name "unconnected-(XS3-Pad113)_1") (class "Default")
      (node (ref "XS3") (pin "113") (pintype "passive"))
    )
    (net (code "87") (name "unconnected-(XS3-Pad113)_2") (class "Default")
      (node (ref "XS3") (pin "113") (pintype "passive"))
    )
    (net (code "88") (name "unconnected-(XS3-Pad113)_3") (class "Default")
      (node (ref "XS3") (pin "113") (pintype "passive"))
    )
    (net (code "89") (name "unconnected-(XS3-Pad113)_4") (class "Default")
      (node (ref "XS3") (pin "113") (pintype "passive"))
    )
    (net (code "90") (name "unconnected-(XS3-Pad113)_5") (class "Default")
      (node (ref "XS3") (pin "113") (pintype "passive"))
    )
    (net (code "91") (name "unconnected-(XS3-Pad113)_6") (class "Default")
      (node (ref "XS3") (pin "113") (pintype "passive"))
    )
    (net (code "92") (name "unconnected-(XS3-Pad113)_7") (class "Default")
      (node (ref "XS3") (pin "113") (pintype "passive"))
    )
    (net (code "93") (name "unconnected-(XS3-Pad114)") (class "Default")
      (node (ref "XS3") (pin "114") (pintype "passive"))
    )
    (net (code "94") (name "unconnected-(XS3-Pad114)_1") (class "Default")
      (node (ref "XS3") (pin "114") (pintype "passive"))
    )
    (net (code "95") (name "unconnected-(XS3-Pad114)_2") (class "Default")
      (node (ref "XS3") (pin "114") (pintype "passive"))
    )
    (net (code "96") (name "unconnected-(XS3-Pad114)_3") (class "Default")
      (node (ref "XS3") (pin "114") (pintype "passive"))
    )
    (net (code "97") (name "unconnected-(XS3-Pad114)_4") (class "Default")
      (node (ref "XS3") (pin "114") (pintype "passive"))
    )
    (net (code "98") (name "unconnected-(XS3-Pad114)_5") (class "Default")
      (node (ref "XS3") (pin "114") (pintype "passive"))
    )
    (net (code "99") (name "unconnected-(XS3-Pad114)_6") (class "Default")
      (node (ref "XS3") (pin "114") (pintype "passive"))
    )
    (net (code "100") (name "unconnected-(XS3-Pad114)_7") (class "Default")
      (node (ref "XS3") (pin "114") (pintype "passive"))
    )
    (net (code "101") (name "unconnected-(XS3-Pad115)") (class "Default")
      (node (ref "XS3") (pin "115") (pintype "passive"))
    )
    (net (code "102") (name "unconnected-(XS3-Pad115)_1") (class "Default")
      (node (ref "XS3") (pin "115") (pintype "passive"))
    )
    (net (code "103") (name "unconnected-(XS3-Pad115)_2") (class "Default")
      (node (ref "XS3") (pin "115") (pintype "passive"))
    )
    (net (code "104") (name "unconnected-(XS3-Pad115)_3") (class "Default")
      (node (ref "XS3") (pin "115") (pintype "passive"))
    )
    (net (code "105") (name "unconnected-(XS3-Pad115)_4") (class "Default")
      (node (ref "XS3") (pin "115") (pintype "passive"))
    )
    (net (code "106") (name "unconnected-(XS3-Pad115)_5") (class "Default")
      (node (ref "XS3") (pin "115") (pintype "passive"))
    )
    (net (code "107") (name "unconnected-(XS3-Pad115)_6") (class "Default")
      (node (ref "XS3") (pin "115") (pintype "passive"))
    )
    (net (code "108") (name "unconnected-(XS3-Pad115)_7") (class "Default")
      (node (ref "XS3") (pin "115") (pintype "passive"))
    )
    (net (code "109") (name "unconnected-(XS3-Pad116)") (class "Default")
      (node (ref "XS3") (pin "116") (pintype "passive+no_connect"))
    )
    (net (code "110") (name "unconnected-(XS3-Pad116)") (class "Default")
      (node (ref "XS3") (pin "116") (pintype "passive"))
    )
    (net (code "111") (name "unconnected-(XS3-Pad116)_1") (class "Default")
      (node (ref "XS3") (pin "116") (pintype "passive"))
    )
    (net (code "112") (name "unconnected-(XS3-Pad116)_2") (class "Default")
      (node (ref "XS3") (pin "116") (pintype "passive"))
    )
    (net (code "113") (name "unconnected-(XS3-Pad116)_3") (class "Default")
      (node (ref "XS3") (pin "116") (pintype "passive"))
    )
    (net (code "114") (name "unconnected-(XS3-Pad116)_4") (class "Default")
      (node (ref "XS3") (pin "116") (pintype "passive"))
    )
    (net (code "115") (name "unconnected-(XS3-Pad116)_5") (class "Default")
      (node (ref "XS3") (pin "116") (pintype "passive"))
    )
    (net (code "116") (name "unconnected-(XS3-Pad116)_6") (class "Default")
      (node (ref "XS3") (pin "116") (pintype "passive"))
    )
    (net (code "117") (name "unconnected-(XS3-Pad116)_7") (class "Default")
      (node (ref "XS3") (pin "116") (pintype "passive"))
    )
    (net (code "118") (name "unconnected-(XS3-Pad117)") (class "Default")
      (node (ref "XS3") (pin "117") (pintype "passive+no_connect"))
    )
    (net (code "119") (name "unconnected-(XS3-Pad117)") (class "Default")
      (node (ref "XS3") (pin "117") (pintype "passive"))
    )
    (net (code "120") (name "unconnected-(XS3-Pad117)_1") (class "Default")
      (node (ref "XS3") (pin "117") (pintype "passive"))
    )
    (net (code "121") (name "unconnected-(XS3-Pad117)_2") (class "Default")
      (node (ref "XS3") (pin "117") (pintype "passive"))
    )
    (net (code "122") (name "unconnected-(XS3-Pad117)_3") (class "Default")
      (node (ref "XS3") (pin "117") (pintype "passive"))
    )
    (net (code "123") (name "unconnected-(XS3-Pad117)_4") (class "Default")
      (node (ref "XS3") (pin "117") (pintype "passive"))
    )
    (net (code "124") (name "unconnected-(XS3-Pad117)_5") (class "Default")
      (node (ref "XS3") (pin "117") (pintype "passive"))
    )
    (net (code "125") (name "unconnected-(XS3-Pad117)_6") (class "Default")
      (node (ref "XS3") (pin "117") (pintype "passive"))
    )
    (net (code "126") (name "unconnected-(XS3-Pad117)_7") (class "Default")
      (node (ref "XS3") (pin "117") (pintype "passive"))
    )
    (net (code "127") (name "unconnected-(XS3-Pad118)") (class "Default")
      (node (ref "XS3") (pin "118") (pintype "passive"))
    )
    (net (code "128") (name "unconnected-(XS3-Pad118)") (class "Default")
      (node (ref "XS3") (pin "118") (pintype "passive+no_connect"))
    )
    (net (code "129") (name "unconnected-(XS3-Pad118)_1") (class "Default")
      (node (ref "XS3") (pin "118") (pintype "passive"))
    )
    (net (code "130") (name "unconnected-(XS3-Pad118)_2") (class "Default")
      (node (ref "XS3") (pin "118") (pintype "passive"))
    )
    (net (code "131") (name "unconnected-(XS3-Pad118)_3") (class "Default")
      (node (ref "XS3") (pin "118") (pintype "passive"))
    )
    (net (code "132") (name "unconnected-(XS3-Pad118)_4") (class "Default")
      (node (ref "XS3") (pin "118") (pintype "passive"))
    )
    (net (code "133") (name "unconnected-(XS3-Pad118)_5") (class "Default")
      (node (ref "XS3") (pin "118") (pintype "passive"))
    )
    (net (code "134") (name "unconnected-(XS3-Pad118)_6") (class "Default")
      (node (ref "XS3") (pin "118") (pintype "passive"))
    )
    (net (code "135") (name "unconnected-(XS3-Pad118)_7") (class "Default")
      (node (ref "XS3") (pin "118") (pintype "passive"))
    )
    (net (code "136") (name "unconnected-(XS3-Pad119)") (class "Default")
      (node (ref "XS3") (pin "119") (pintype "passive"))
    )
    (net (code "137") (name "unconnected-(XS3-Pad119)_1") (class "Default")
      (node (ref "XS3") (pin "119") (pintype "passive"))
    )
    (net (code "138") (name "unconnected-(XS3-Pad119)_2") (class "Default")
      (node (ref "XS3") (pin "119") (pintype "passive"))
    )
    (net (code "139") (name "unconnected-(XS3-Pad119)_3") (class "Default")
      (node (ref "XS3") (pin "119") (pintype "passive"))
    )
    (net (code "140") (name "unconnected-(XS3-Pad119)_4") (class "Default")
      (node (ref "XS3") (pin "119") (pintype "passive"))
    )
    (net (code "141") (name "unconnected-(XS3-Pad119)_5") (class "Default")
      (node (ref "XS3") (pin "119") (pintype "passive"))
    )
    (net (code "142") (name "unconnected-(XS3-Pad119)_6") (class "Default")
      (node (ref "XS3") (pin "119") (pintype "passive"))
    )
    (net (code "143") (name "unconnected-(XS3-Pad119)_7") (class "Default")
      (node (ref "XS3") (pin "119") (pintype "passive"))
    )
    (net (code "144") (name "unconnected-(XS3-Pad120)") (class "Default")
      (node (ref "XS3") (pin "120") (pintype "passive"))
    )
    (net (code "145") (name "unconnected-(XS3-Pad120)_1") (class "Default")
      (node (ref "XS3") (pin "120") (pintype "passive"))
    )
    (net (code "146") (name "unconnected-(XS3-Pad120)_2") (class "Default")
      (node (ref "XS3") (pin "120") (pintype "passive"))
    )
    (net (code "147") (name "unconnected-(XS3-Pad120)_3") (class "Default")
      (node (ref "XS3") (pin "120") (pintype "passive"))
    )
    (net (code "148") (name "unconnected-(XS3-Pad120)_4") (class "Default")
      (node (ref "XS3") (pin "120") (pintype "passive"))
    )
    (net (code "149") (name "unconnected-(XS3-Pad120)_5") (class "Default")
      (node (ref "XS3") (pin "120") (pintype "passive"))
    )
    (net (code "150") (name "unconnected-(XS3-Pad120)_6") (class "Default")
      (node (ref "XS3") (pin "120") (pintype "passive"))
    )
    (net (code "151") (name "unconnected-(XS3-Pad120)_7") (class "Default")
      (node (ref "XS3") (pin "120") (pintype "passive"))
    )
    (net (code "152") (name "unconnected-(XS3-Pad121)") (class "Default")
      (node (ref "XS3") (pin "121") (pintype "passive"))
    )
    (net (code "153") (name "unconnected-(XS3-Pad121)_1") (class "Default")
      (node (ref "XS3") (pin "121") (pintype "passive"))
    )
    (net (code "154") (name "unconnected-(XS3-Pad121)_2") (class "Default")
      (node (ref "XS3") (pin "121") (pintype "passive"))
    )
    (net (code "155") (name "unconnected-(XS3-Pad121)_3") (class "Default")
      (node (ref "XS3") (pin "121") (pintype "passive"))
    )
    (net (code "156") (name "unconnected-(XS3-Pad121)_4") (class "Default")
      (node (ref "XS3") (pin "121") (pintype "passive"))
    )
    (net (code "157") (name "unconnected-(XS3-Pad121)_5") (class "Default")
      (node (ref "XS3") (pin "121") (pintype "passive"))
    )
    (net (code "158") (name "unconnected-(XS3-Pad121)_6") (class "Default")
      (node (ref "XS3") (pin "121") (pintype "passive"))
    )
    (net (code "159") (name "unconnected-(XS3-Pad121)_7") (class "Default")
      (node (ref "XS3") (pin "121") (pintype "passive"))
    )
    (net (code "160") (name "unconnected-(XS3-PadA11)") (class "Default")
      (node (ref "XS3") (pin "A11") (pintype "passive"))
    )
    (net (code "161") (name "unconnected-(XS3-PadA12)") (class "Default")
      (node (ref "XS3") (pin "A12") (pintype "passive"))
    )
    (net (code "162") (name "unconnected-(XS3-PadA13)") (class "Default")
      (node (ref "XS3") (pin "A13") (pintype "passive"))
    )
    (net (code "163") (name "unconnected-(XS3-PadA14)") (class "Default")
      (node (ref "XS3") (pin "A14") (pintype "passive"))
    )
    (net (code "164") (name "unconnected-(XS3-PadB25)") (class "Default")
      (node (ref "XS3") (pin "B25") (pintype "passive"))
    )
    (net (code "165") (name "unconnected-(XS3-PadB26)") (class "Default")
      (node (ref "XS3") (pin "B26") (pintype "passive"))
    )
    (net (code "166") (name "unconnected-(XS3-PadB27)") (class "Default")
      (node (ref "XS3") (pin "B27") (pintype "passive"))
    )
    (net (code "167") (name "unconnected-(XS3-PadB28)") (class "Default")
      (node (ref "XS3") (pin "B28") (pintype "passive"))
    )
    (net (code "168") (name "unconnected-(XS3-PadC39)") (class "Default")
      (node (ref "XS3") (pin "C39") (pintype "passive"))
    )
    (net (code "169") (name "unconnected-(XS3-PadC40)") (class "Default")
      (node (ref "XS3") (pin "C40") (pintype "passive"))
    )
    (net (code "170") (name "unconnected-(XS3-PadC41)") (class "Default")
      (node (ref "XS3") (pin "C41") (pintype "passive"))
    )
    (net (code "171") (name "unconnected-(XS3-PadC42)") (class "Default")
      (node (ref "XS3") (pin "C42") (pintype "passive"))
    )
    (net (code "172") (name "unconnected-(XS3-PadD53)") (class "Default")
      (node (ref "XS3") (pin "D53") (pintype "passive"))
    )
    (net (code "173") (name "unconnected-(XS3-PadD54)") (class "Default")
      (node (ref "XS3") (pin "D54") (pintype "passive"))
    )
    (net (code "174") (name "unconnected-(XS3-PadD55)") (class "Default")
      (node (ref "XS3") (pin "D55") (pintype "passive"))
    )
    (net (code "175") (name "unconnected-(XS3-PadD56)") (class "Default")
      (node (ref "XS3") (pin "D56") (pintype "passive"))
    )
    (net (code "176") (name "unconnected-(XS3-PadE67)") (class "Default")
      (node (ref "XS3") (pin "E67") (pintype "passive"))
    )
    (net (code "177") (name "unconnected-(XS3-PadE68)") (class "Default")
      (node (ref "XS3") (pin "E68") (pintype "passive"))
    )
    (net (code "178") (name "unconnected-(XS3-PadE69)") (class "Default")
      (node (ref "XS3") (pin "E69") (pintype "passive"))
    )
    (net (code "179") (name "unconnected-(XS3-PadE70)") (class "Default")
      (node (ref "XS3") (pin "E70") (pintype "passive"))
    )
    (net (code "180") (name "unconnected-(XS3-PadF81)") (class "Default")
      (node (ref "XS3") (pin "F81") (pintype "passive"))
    )
    (net (code "181") (name "unconnected-(XS3-PadF82)") (class "Default")
      (node (ref "XS3") (pin "F82") (pintype "passive"))
    )
    (net (code "182") (name "unconnected-(XS3-PadF83)") (class "Default")
      (node (ref "XS3") (pin "F83") (pintype "passive"))
    )
    (net (code "183") (name "unconnected-(XS3-PadF84)") (class "Default")
      (node (ref "XS3") (pin "F84") (pintype "passive"))
    )
    (net (code "184") (name "unconnected-(XS3-PadG95)") (class "Default")
      (node (ref "XS3") (pin "G95") (pintype "passive"))
    )
    (net (code "185") (name "unconnected-(XS3-PadG96)") (class "Default")
      (node (ref "XS3") (pin "G96") (pintype "passive"))
    )
    (net (code "186") (name "unconnected-(XS3-PadG97)") (class "Default")
      (node (ref "XS3") (pin "G97") (pintype "passive"))
    )
    (net (code "187") (name "unconnected-(XS3-PadG98)") (class "Default")
      (node (ref "XS3") (pin "G98") (pintype "passive"))
    )
    (net (code "188") (name "unconnected-(XS3-PadH109)") (class "Default")
      (node (ref "XS3") (pin "H109") (pintype "passive"))
    )
    (net (code "189") (name "unconnected-(XS3-PadH110)") (class "Default")
      (node (ref "XS3") (pin "H110") (pintype "passive"))
    )
    (net (code "190") (name "unconnected-(XS3-PadH111)") (class "Default")
      (node (ref "XS3") (pin "H111") (pintype "passive"))
    )
    (net (code "191") (name "unconnected-(XS3-PadH112)") (class "Default")
      (node (ref "XS3") (pin "H112") (pintype "passive"))
    )
  )
)
